# mk312lite_V4.net
KiCad netlist of a schematic drawn in EAGLE
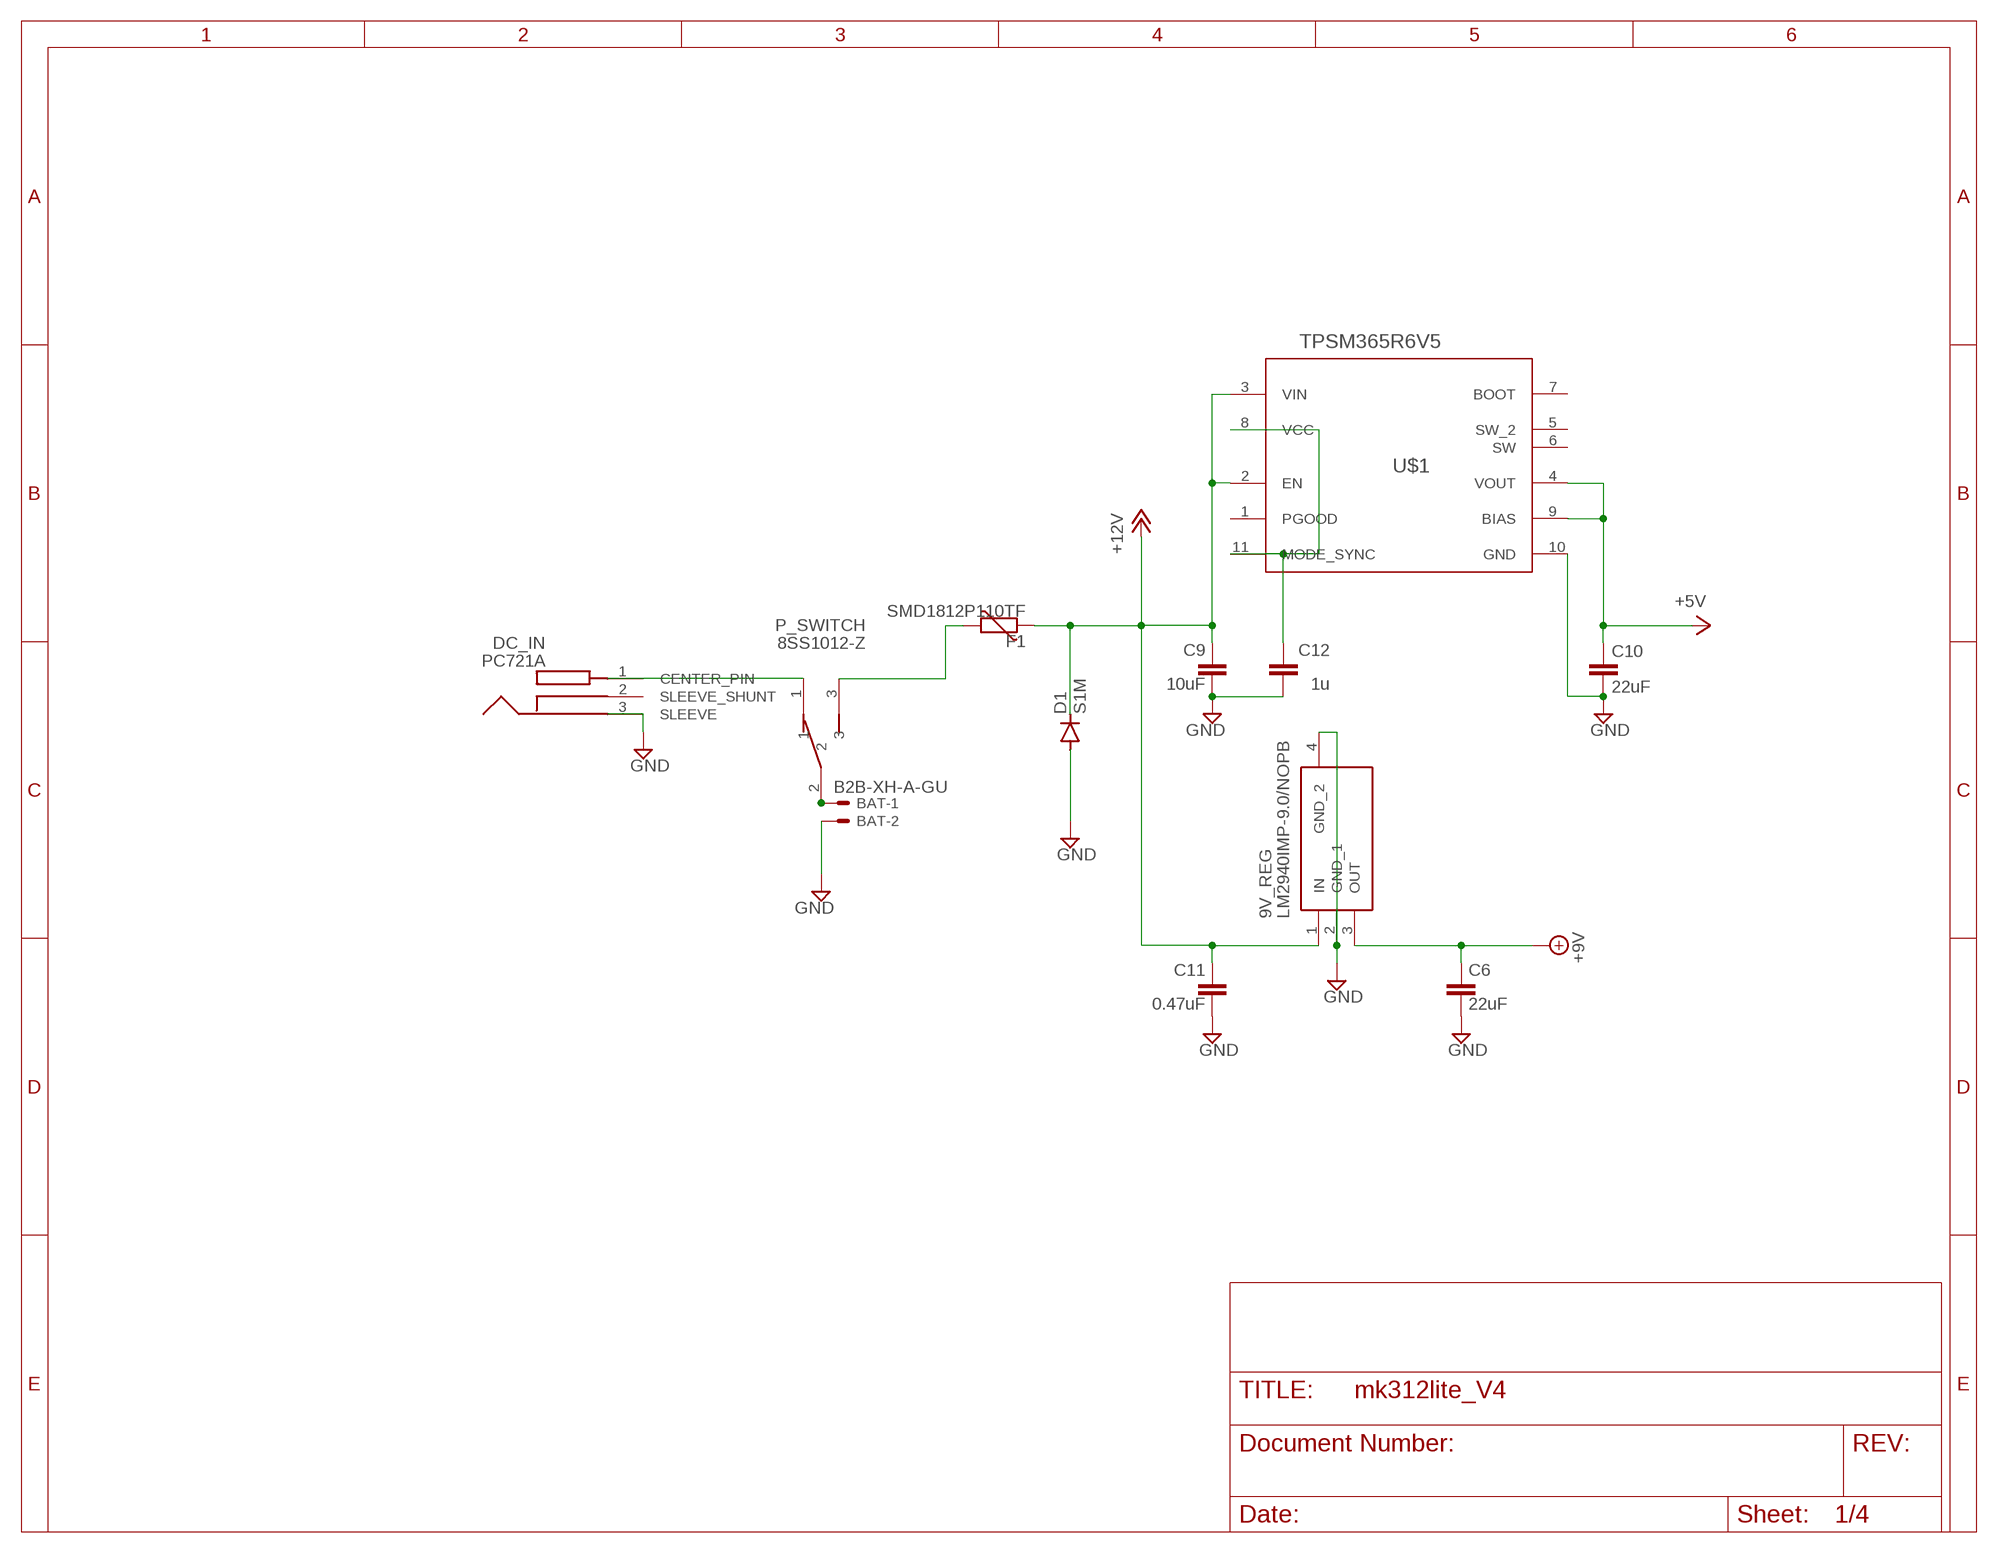
[diagram p0: schematic, sheet 1]
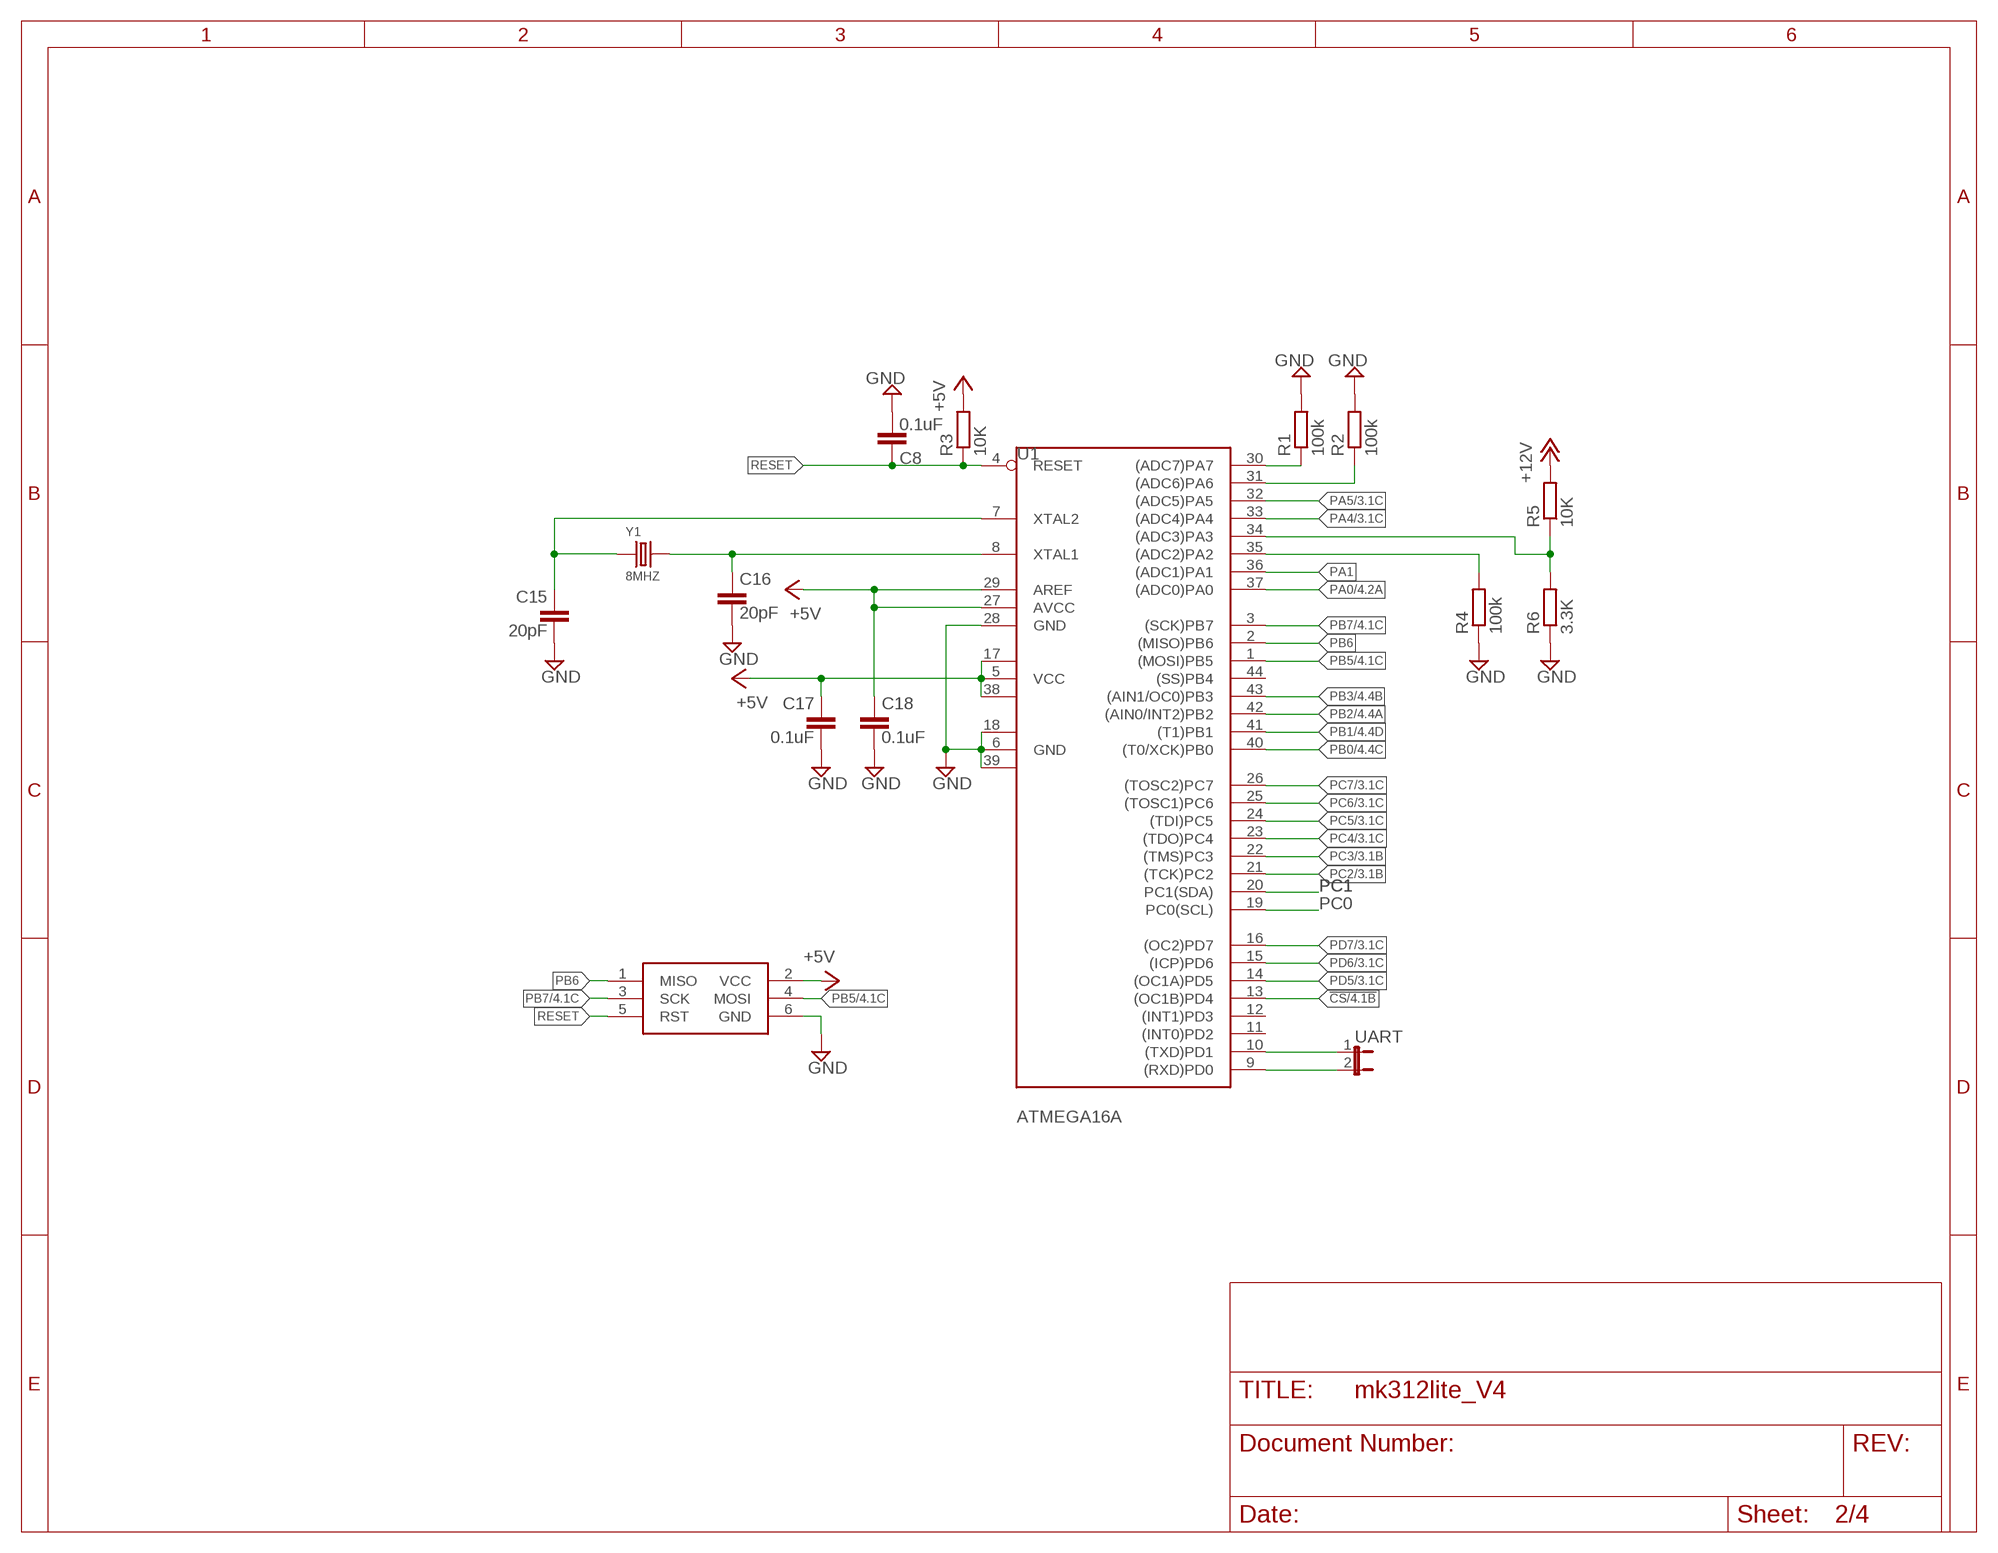
[diagram p1: schematic, sheet 2]
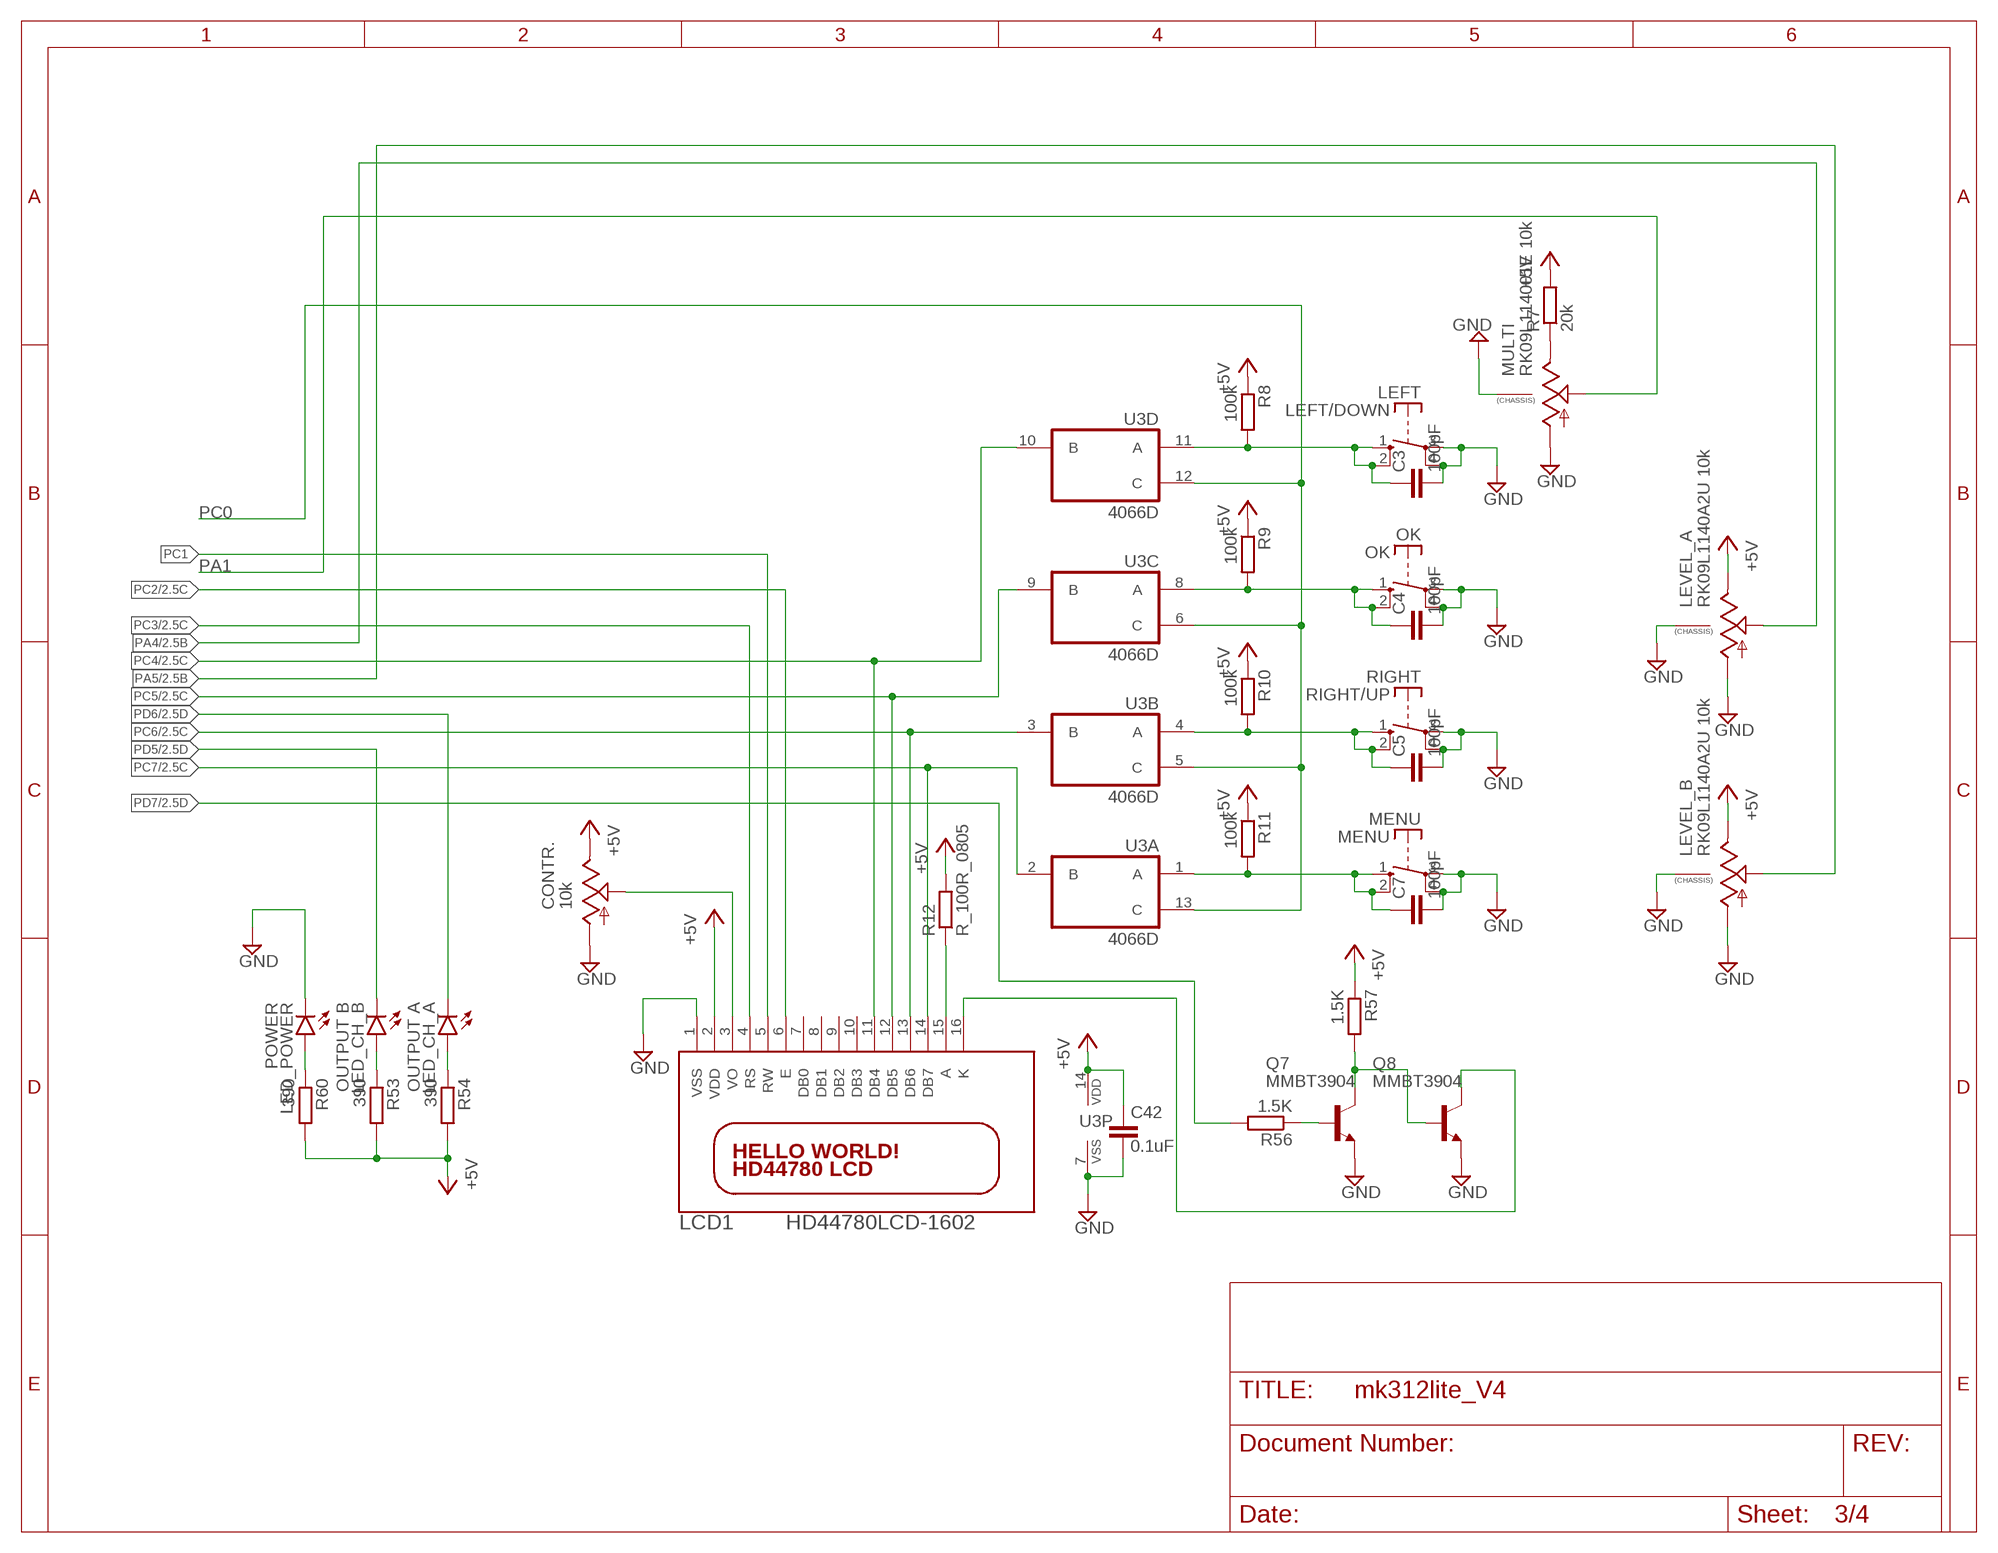
[diagram p2: schematic, sheet 3]
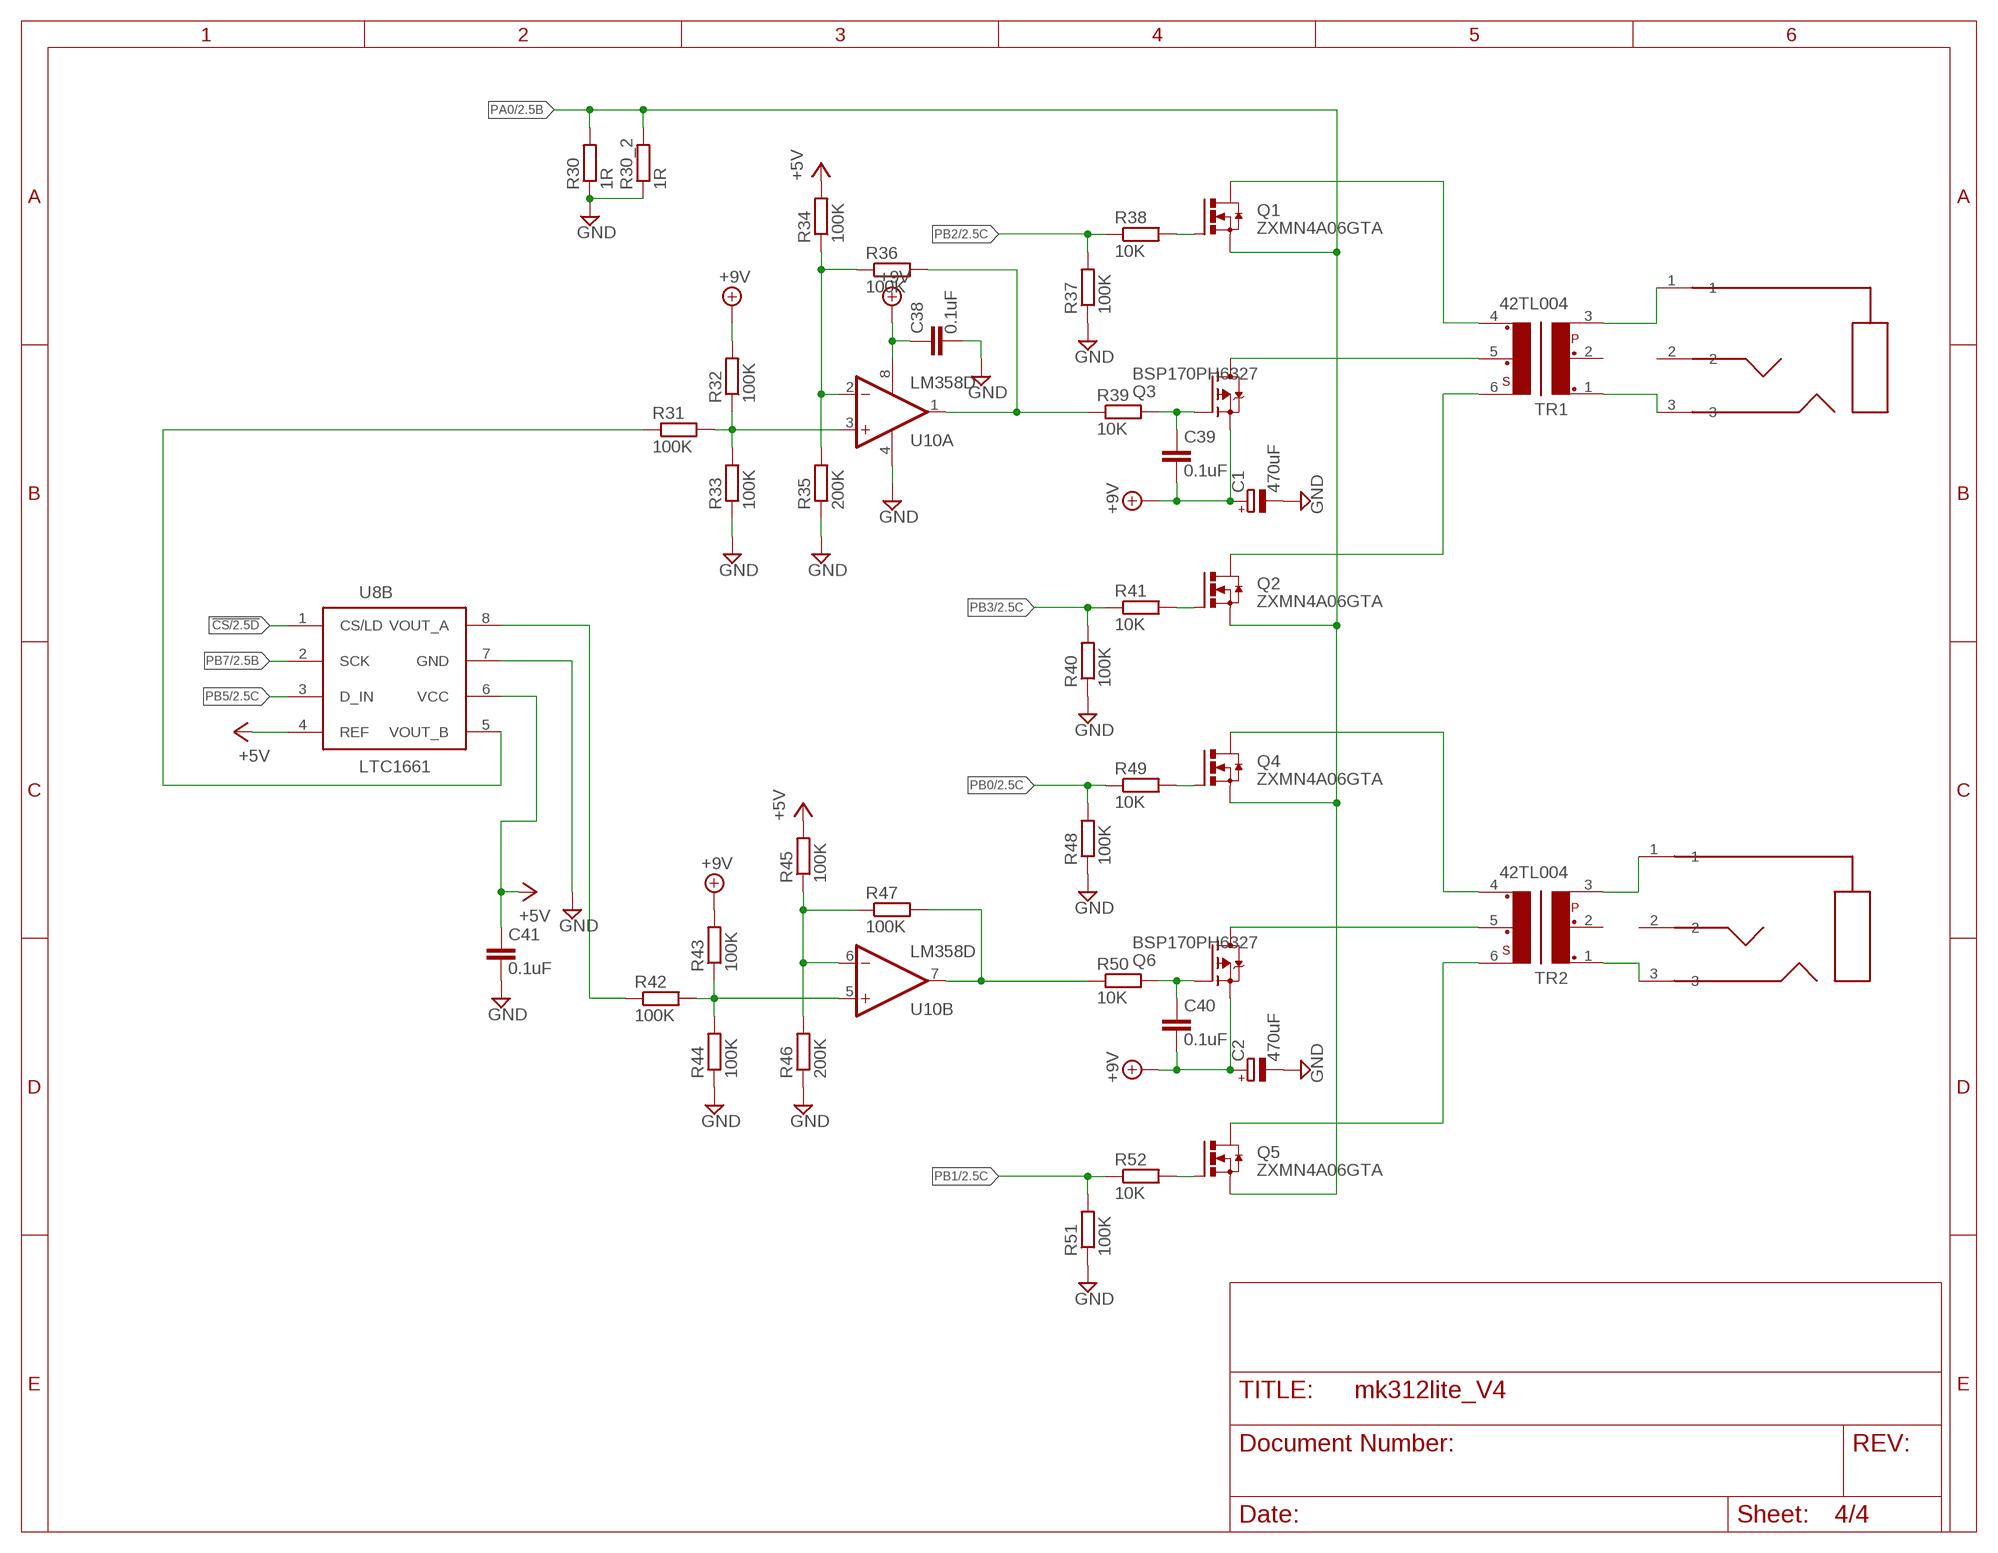
[diagram p3: schematic, sheet 4]

(export (version "E")
  (design (tool "Eeschema 10.0.6"))
  (components
    (comp (ref "9V_REG")
      (value "LM2940IMP-9.0/NOPB")
      (footprint "eagle-import:SOT230P700X180-4N")
      (fields (field (name "MOUSER_PART_NUMBER") "926-LM2940IMP90NOPB"))
      (libsource (lib "eagle-import") (part "LM2940IMP-9.0_NOPB"))
    )
    (comp (ref "BAT")
      (value "B2B-XH-A-GU")
      (footprint "eagle-import:JST-XH-02-PACKAGE-LONG-PAD")
      (libsource (lib "eagle-import") (part "JST-XH-02-PIN-LONG-PAD"))
    )
    (comp (ref "C6")
      (value "22uF")
      (footprint "eagle-import:C1206")
      (libsource (lib "eagle-import") (part "C-EUC1206"))
    )
    (comp (ref "C9")
      (value "10uF")
      (footprint "eagle-import:C0805")
      (libsource (lib "eagle-import") (part "C-EUC0805"))
    )
    (comp (ref "C10")
      (value "22uF")
      (footprint "eagle-import:C1206")
      (libsource (lib "eagle-import") (part "C-EUC1206"))
    )
    (comp (ref "C11")
      (value "0.47uF")
      (footprint "eagle-import:C0805")
      (libsource (lib "eagle-import") (part "C-EUC0805"))
    )
    (comp (ref "C12")
      (value "1u")
      (footprint "eagle-import:C0805")
      (libsource (lib "eagle-import") (part "C-EUC0805"))
    )
    (comp (ref "D1")
      (value "S1M")
      (footprint "eagle-import:SMA")
      (libsource (lib "eagle-import") (part "S1M"))
    )
    (comp (ref "DC_IN")
      (value "PC721A")
      (footprint "eagle-import:PC721A")
      (fields (field (name "MOUSER_PART_NUMBER") "502-PC721A"))
      (libsource (lib "eagle-import") (part "PC721A"))
    )
    (comp (ref "F1")
      (value "SMD1812P110TF")
      (footprint "eagle-import:CT_CN1812")
      (libsource (lib "eagle-import") (part "VARISTORCN1812"))
    )
    (comp (ref "P_SWITCH")
      (value "8SS1012-Z")
      (footprint "eagle-import:8SS1012Z")
      (libsource (lib "eagle-import") (part "8SS1012-Z"))
    )
    (comp (ref "U$1")
      (value "TPSM365R6V5")
      (footprint "eagle-import:RDN0011A-MFG")
      (fields
        (field (name "MANUFACTURER_PART_NUMBER") "PTPSM365R6FRDN")
        (field (name "COPYRIGHT") "Copyright (C) 2025 Ultra Librarian. All rights reserved.")
      )
      (libsource (lib "eagle-import") (part "PTPSM365R6FRDN"))
    )
    (comp (ref "C1")
      (value "470uF")
      (footprint "eagle-import:150CLZ-1010")
      (libsource (lib "eagle-import") (part "CPOL-EU150CLZ-1010"))
    )
    (comp (ref "C2")
      (value "470uF")
      (footprint "eagle-import:150CLZ-1010")
      (libsource (lib "eagle-import") (part "CPOL-EU150CLZ-1010"))
    )
    (comp (ref "C38")
      (value "0.1uF")
      (footprint "eagle-import:C0805")
      (libsource (lib "eagle-import") (part "C-EUC0805"))
    )
    (comp (ref "C39")
      (value "0.1uF")
      (footprint "eagle-import:C0805")
      (libsource (lib "eagle-import") (part "C-EUC0805"))
    )
    (comp (ref "C40")
      (value "0.1uF")
      (footprint "eagle-import:C0805")
      (libsource (lib "eagle-import") (part "C-EUC0805"))
    )
    (comp (ref "C41")
      (value "0.1uF")
      (footprint "eagle-import:C0805")
      (libsource (lib "eagle-import") (part "C-EUC0805"))
    )
    (comp (ref "CHAN_A")
      (value "PJ-301C")
      (footprint "eagle-import:PJ-301C")
      (libsource (lib "eagle-import") (part "PC-301C"))
    )
    (comp (ref "CHAN_B")
      (value "PJ-301C")
      (footprint "eagle-import:PJ-301C")
      (libsource (lib "eagle-import") (part "PC-301C"))
    )
    (comp (ref "Q1")
      (value "ZXMN4A06GTA")
      (footprint "eagle-import:SOT223")
      (libsource (lib "eagle-import") (part "N-HEXFET-2D_?-SOT232IRLL2705"))
    )
    (comp (ref "Q2")
      (value "ZXMN4A06GTA")
      (footprint "eagle-import:SOT223")
      (libsource (lib "eagle-import") (part "N-HEXFET-2D_?-SOT232IRLL2705"))
    )
    (comp (ref "Q3")
      (value "BSP170PH6327")
      (footprint "eagle-import:SOT230P700X180-4N")
      (libsource (lib "eagle-import") (part "IRFL9014TRPBF"))
    )
    (comp (ref "Q4")
      (value "ZXMN4A06GTA")
      (footprint "eagle-import:SOT223")
      (libsource (lib "eagle-import") (part "N-HEXFET-2D_?-SOT232IRLL2705"))
    )
    (comp (ref "Q5")
      (value "ZXMN4A06GTA")
      (footprint "eagle-import:SOT223")
      (libsource (lib "eagle-import") (part "N-HEXFET-2D_?-SOT232IRLL2705"))
    )
    (comp (ref "Q6")
      (value "BSP170PH6327")
      (footprint "eagle-import:SOT230P700X180-4N")
      (libsource (lib "eagle-import") (part "IRFL9014TRPBF"))
    )
    (comp (ref "R30")
      (value "1R")
      (footprint "eagle-import:R1206")
      (libsource (lib "eagle-import") (part "R-EU_R1206"))
    )
    (comp (ref "R30_2")
      (value "1R")
      (footprint "eagle-import:R1206")
      (libsource (lib "eagle-import") (part "R-EU_R1206"))
    )
    (comp (ref "R31")
      (value "100K")
      (footprint "eagle-import:R0805")
      (libsource (lib "eagle-import") (part "R-EU_R0805"))
    )
    (comp (ref "R32")
      (value "100K")
      (footprint "eagle-import:R0805")
      (libsource (lib "eagle-import") (part "R-EU_R0805"))
    )
    (comp (ref "R33")
      (value "100K")
      (footprint "eagle-import:R0805")
      (libsource (lib "eagle-import") (part "R-EU_R0805"))
    )
    (comp (ref "R34")
      (value "100K")
      (footprint "eagle-import:R0805")
      (libsource (lib "eagle-import") (part "R-EU_R0805"))
    )
    (comp (ref "R35")
      (value "200K")
      (footprint "eagle-import:R0805")
      (libsource (lib "eagle-import") (part "R-EU_R0805"))
    )
    (comp (ref "R36")
      (value "100K")
      (footprint "eagle-import:R0805")
      (libsource (lib "eagle-import") (part "R-EU_R0805"))
    )
    (comp (ref "R37")
      (value "100K")
      (footprint "eagle-import:R0805")
      (libsource (lib "eagle-import") (part "R-EU_R0805"))
    )
    (comp (ref "R38")
      (value "10K")
      (footprint "eagle-import:R0805")
      (libsource (lib "eagle-import") (part "R-EU_R0805"))
    )
    (comp (ref "R39")
      (value "10K")
      (footprint "eagle-import:R0805")
      (libsource (lib "eagle-import") (part "R-EU_R0805"))
    )
    (comp (ref "R40")
      (value "100K")
      (footprint "eagle-import:R0805")
      (libsource (lib "eagle-import") (part "R-EU_R0805"))
    )
    (comp (ref "R41")
      (value "10K")
      (footprint "eagle-import:R0805")
      (libsource (lib "eagle-import") (part "R-EU_R0805"))
    )
    (comp (ref "R42")
      (value "100K")
      (footprint "eagle-import:R0805")
      (libsource (lib "eagle-import") (part "R-EU_R0805"))
    )
    (comp (ref "R43")
      (value "100K")
      (footprint "eagle-import:R0805")
      (libsource (lib "eagle-import") (part "R-EU_R0805"))
    )
    (comp (ref "R44")
      (value "100K")
      (footprint "eagle-import:R0805")
      (libsource (lib "eagle-import") (part "R-EU_R0805"))
    )
    (comp (ref "R45")
      (value "100K")
      (footprint "eagle-import:R0805")
      (libsource (lib "eagle-import") (part "R-EU_R0805"))
    )
    (comp (ref "R46")
      (value "200K")
      (footprint "eagle-import:R0805")
      (libsource (lib "eagle-import") (part "R-EU_R0805"))
    )
    (comp (ref "R47")
      (value "100K")
      (footprint "eagle-import:R0805")
      (libsource (lib "eagle-import") (part "R-EU_R0805"))
    )
    (comp (ref "R48")
      (value "100K")
      (footprint "eagle-import:R0805")
      (libsource (lib "eagle-import") (part "R-EU_R0805"))
    )
    (comp (ref "R49")
      (value "10K")
      (footprint "eagle-import:R0805")
      (libsource (lib "eagle-import") (part "R-EU_R0805"))
    )
    (comp (ref "R50")
      (value "10K")
      (footprint "eagle-import:R0805")
      (libsource (lib "eagle-import") (part "R-EU_R0805"))
    )
    (comp (ref "R51")
      (value "100K")
      (footprint "eagle-import:R0805")
      (libsource (lib "eagle-import") (part "R-EU_R0805"))
    )
    (comp (ref "R52")
      (value "10K")
      (footprint "eagle-import:R0805")
      (libsource (lib "eagle-import") (part "R-EU_R0805"))
    )
    (comp (ref "TR1")
      (value "42TL004")
      (footprint "eagle-import:42TL")
      (libsource (lib "eagle-import") (part "42T?L023"))
    )
    (comp (ref "TR2")
      (value "42TL004")
      (footprint "eagle-import:42TL")
      (libsource (lib "eagle-import") (part "42T?L023"))
    )
    (comp (ref "U8B")
      (value "LTC1661")
      (footprint "eagle-import:MSOP8")
      (libsource (lib "eagle-import") (part "LTC1661IMS8"))
    )
    (comp (ref "U10")
      (value "LM358D")
      (footprint "eagle-import:SO08")
      (libsource (lib "eagle-import") (part "LM358D"))
    )
    (comp (ref "C8")
      (value "0.1uF")
      (footprint "eagle-import:C0805")
      (libsource (lib "eagle-import") (part "C-EUC0805"))
    )
    (comp (ref "C15")
      (value "20pF")
      (footprint "eagle-import:C0603")
      (libsource (lib "eagle-import") (part "C-EUC0603"))
    )
    (comp (ref "C16")
      (value "20pF")
      (footprint "eagle-import:C0603")
      (libsource (lib "eagle-import") (part "C-EUC0603"))
    )
    (comp (ref "C17")
      (value "0.1uF")
      (footprint "eagle-import:C0805")
      (libsource (lib "eagle-import") (part "C-EUC0805"))
    )
    (comp (ref "C18")
      (value "0.1uF")
      (footprint "eagle-import:C0805")
      (libsource (lib "eagle-import") (part "C-EUC0805"))
    )
    (comp (ref "ISP1")
      (value "AVRISP-6")
      (footprint "eagle-import:AVRISP")
      (libsource (lib "eagle-import") (part "AVRISP-6"))
    )
    (comp (ref "R1")
      (value "100k")
      (footprint "eagle-import:R0805")
      (libsource (lib "eagle-import") (part "R-EU_R0805"))
    )
    (comp (ref "R2")
      (value "100k")
      (footprint "eagle-import:R0805")
      (libsource (lib "eagle-import") (part "R-EU_R0805"))
    )
    (comp (ref "R3")
      (value "10K")
      (footprint "eagle-import:R0805")
      (libsource (lib "eagle-import") (part "R-EU_R0805"))
    )
    (comp (ref "R4")
      (value "100k")
      (footprint "eagle-import:R0805")
      (libsource (lib "eagle-import") (part "R-EU_R0805"))
    )
    (comp (ref "R5")
      (value "10K")
      (footprint "eagle-import:R0805")
      (libsource (lib "eagle-import") (part "R-EU_R0805"))
    )
    (comp (ref "R6")
      (value "3.3K")
      (footprint "eagle-import:R0805")
      (libsource (lib "eagle-import") (part "R-EU_R0805"))
    )
    (comp (ref "U1")
      (value "ATMEGA16A")
      (footprint "eagle-import:TQFP44")
      (fields (field (name "MPN") "ATMEGA16-16AU"))
      (libsource (lib "eagle-import") (part "MEGA16-A"))
    )
    (comp (ref "UART")
      (value "JP1E")
      (footprint "eagle-import:JP1")
      (libsource (lib "eagle-import") (part "JP1E"))
    )
    (comp (ref "Y1")
      (value "8MHZ")
      (footprint "eagle-import:X2-SMD-5.0X3.2X1.3MM")
      (fields (field (name "MPN") "5032/2P"))
      (libsource (lib "eagle-import") (part "SMD-CRYSTAL-8MHZ-20PF-20PPM(2P-5.0X3.2MM)"))
    )
    (comp (ref "C3")
      (value "100pF")
      (footprint "eagle-import:C0805")
      (libsource (lib "eagle-import") (part "C-EUC0805"))
    )
    (comp (ref "C4")
      (value "100pF")
      (footprint "eagle-import:C0805")
      (libsource (lib "eagle-import") (part "C-EUC0805"))
    )
    (comp (ref "C5")
      (value "100pF")
      (footprint "eagle-import:C0805")
      (libsource (lib "eagle-import") (part "C-EUC0805"))
    )
    (comp (ref "C7")
      (value "100pF")
      (footprint "eagle-import:C0805")
      (libsource (lib "eagle-import") (part "C-EUC0805"))
    )
    (comp (ref "C42")
      (value "0.1uF")
      (footprint "eagle-import:C0805")
      (libsource (lib "eagle-import") (part "C-EUC0805"))
    )
    (comp (ref "CONTR.")
      (value "10k")
      (footprint "eagle-import:B25P")
      (libsource (lib "eagle-import") (part "TRIM_US-B25P"))
    )
    (comp (ref "LCD1")
      (value "HD44780LCD-1602")
      (footprint "eagle-import:LCD1602")
      (libsource (lib "eagle-import") (part "HD44780LCD-1602"))
    )
    (comp (ref "LED_CH_A")
      (value "OUTPUT A")
      (footprint "eagle-import:LED3MM")
      (libsource (lib "eagle-import") (part "LED3MM"))
    )
    (comp (ref "LED_CH_B")
      (value "OUTPUT B")
      (footprint "eagle-import:LED3MM")
      (libsource (lib "eagle-import") (part "LED3MM"))
    )
    (comp (ref "LED_POWER")
      (value "POWER")
      (footprint "eagle-import:LED3MM")
      (libsource (lib "eagle-import") (part "LED3MM"))
    )
    (comp (ref "LEFT")
      (value "LEFT/DOWN")
      (footprint "eagle-import:DTE6K")
      (libsource (lib "eagle-import") (part "DTE6K"))
    )
    (comp (ref "LEVEL_A")
      (value "RK09L1140A2U 10k")
      (footprint "eagle-import:9MM_SNAP-IN_POT")
      (libsource (lib "eagle-import") (part "9MM_SNAP-IN_POT_CHASSIS"))
    )
    (comp (ref "LEVEL_B")
      (value "RK09L1140A2U 10k")
      (footprint "eagle-import:9MM_SNAP-IN_POT")
      (libsource (lib "eagle-import") (part "9MM_SNAP-IN_POT_CHASSIS"))
    )
    (comp (ref "MENU")
      (value "MENU")
      (footprint "eagle-import:DTE6K")
      (libsource (lib "eagle-import") (part "DTE6K"))
    )
    (comp (ref "MULTI")
      (value "RK09L114001E 10k")
      (footprint "eagle-import:9MM_SNAP-IN_POT")
      (libsource (lib "eagle-import") (part "9MM_SNAP-IN_POT_CHASSIS"))
    )
    (comp (ref "OK")
      (value "OK")
      (footprint "eagle-import:DTE6K")
      (libsource (lib "eagle-import") (part "DTE6K"))
    )
    (comp (ref "Q7")
      (value "MMBT3904")
      (footprint "eagle-import:SOT23-BEC")
      (libsource (lib "eagle-import") (part "-NPN-SOT23-BECMMBT3904LT1"))
    )
    (comp (ref "Q8")
      (value "MMBT3904")
      (footprint "eagle-import:SOT23-BEC")
      (libsource (lib "eagle-import") (part "-NPN-SOT23-BECMMBT3904LT1"))
    )
    (comp (ref "R7")
      (value "20k")
      (footprint "eagle-import:R0805")
      (libsource (lib "eagle-import") (part "R-EU_R0805"))
    )
    (comp (ref "R8")
      (value "100k")
      (footprint "eagle-import:R0805")
      (libsource (lib "eagle-import") (part "R-EU_R0805"))
    )
    (comp (ref "R9")
      (value "100k")
      (footprint "eagle-import:R0805")
      (libsource (lib "eagle-import") (part "R-EU_R0805"))
    )
    (comp (ref "R10")
      (value "100k")
      (footprint "eagle-import:R0805")
      (libsource (lib "eagle-import") (part "R-EU_R0805"))
    )
    (comp (ref "R11")
      (value "100k")
      (footprint "eagle-import:R0805")
      (libsource (lib "eagle-import") (part "R-EU_R0805"))
    )
    (comp (ref "R12")
      (value "R_100R_0805")
      (footprint "eagle-import:R0805")
      (fields (field (name "LCSC_PART") "C17408"))
      (libsource (lib "eagle-import") (part "R__0805100R"))
    )
    (comp (ref "R53")
      (value "390")
      (footprint "eagle-import:R0805")
      (libsource (lib "eagle-import") (part "R-EU_R0805"))
    )
    (comp (ref "R54")
      (value "390")
      (footprint "eagle-import:R0805")
      (libsource (lib "eagle-import") (part "R-EU_R0805"))
    )
    (comp (ref "R56")
      (value "1.5K")
      (footprint "eagle-import:R0805")
      (libsource (lib "eagle-import") (part "R-EU_R0805"))
    )
    (comp (ref "R57")
      (value "1.5K")
      (footprint "eagle-import:R0805")
      (libsource (lib "eagle-import") (part "R-EU_R0805"))
    )
    (comp (ref "R60")
      (value "390")
      (footprint "eagle-import:R0805")
      (libsource (lib "eagle-import") (part "R-EU_R0805"))
    )
    (comp (ref "RIGHT")
      (value "RIGHT/UP")
      (footprint "eagle-import:DTE6K")
      (libsource (lib "eagle-import") (part "DTE6K"))
    )
    (comp (ref "U3")
      (value "4066D")
      (footprint "eagle-import:SO14")
      (libsource (lib "eagle-import") (part "4066D"))
    )
  )
  (nets
    (net (code "1") (name "+5V") (class "Default")
      (node (ref "C10") (pin "1") (pinfunction "1_1") (pintype "passive"))
      (node (ref "C17") (pin "1") (pinfunction "1_1") (pintype "passive"))
      (node (ref "C18") (pin "1") (pinfunction "1_1") (pintype "passive"))
      (node (ref "C41") (pin "1") (pinfunction "1_1") (pintype "passive"))
      (node (ref "C42") (pin "1") (pinfunction "1_1") (pintype "passive"))
      (node (ref "CONTR.") (pin "E") (pinfunction "E_E") (pintype "passive"))
      (node (ref "ISP1") (pin "2") (pinfunction "VCC_2") (pintype "power_in"))
      (node (ref "LCD1") (pin "2") (pinfunction "VDD_2") (pintype "power_in"))
      (node (ref "LEVEL_A") (pin "3") (pinfunction "E_3") (pintype "passive"))
      (node (ref "LEVEL_B") (pin "3") (pinfunction "E_3") (pintype "passive"))
      (node (ref "R10") (pin "1") (pinfunction "1_1") (pintype "passive"))
      (node (ref "R11") (pin "1") (pinfunction "1_1") (pintype "passive"))
      (node (ref "R12") (pin "2") (pinfunction "2_2") (pintype "passive"))
      (node (ref "R3") (pin "2") (pinfunction "2_2") (pintype "passive"))
      (node (ref "R34") (pin "2") (pinfunction "2_2") (pintype "passive"))
      (node (ref "R45") (pin "2") (pinfunction "2_2") (pintype "passive"))
      (node (ref "R53") (pin "2") (pinfunction "2_2") (pintype "passive"))
      (node (ref "R54") (pin "2") (pinfunction "2_2") (pintype "passive"))
      (node (ref "R57") (pin "1") (pinfunction "1_1") (pintype "passive"))
      (node (ref "R60") (pin "2") (pinfunction "2_2") (pintype "passive"))
      (node (ref "R7") (pin "2") (pinfunction "2_2") (pintype "passive"))
      (node (ref "R8") (pin "1") (pinfunction "1_1") (pintype "passive"))
      (node (ref "R9") (pin "1") (pinfunction "1_1") (pintype "passive"))
      (node (ref "U$1") (pin "4") (pinfunction "VOUT_4") (pintype "passive"))
      (node (ref "U$1") (pin "9") (pinfunction "BIAS_9") (pintype "passive"))
      (node (ref "U1") (pin "17") (pinfunction "VCC1_17") (pintype "power_in"))
      (node (ref "U1") (pin "27") (pinfunction "AVCC_27") (pintype "power_in"))
      (node (ref "U1") (pin "29") (pinfunction "AREF_29") (pintype "passive"))
      (node (ref "U1") (pin "38") (pinfunction "VCC2_38") (pintype "power_in"))
      (node (ref "U1") (pin "5") (pinfunction "VCC_5") (pintype "power_in"))
      (node (ref "U3") (pin "14") (pinfunction "VDD_14") (pintype "power_in"))
      (node (ref "U8B") (pin "4") (pinfunction "REF_4") (pintype "input"))
      (node (ref "U8B") (pin "6") (pinfunction "VCC_6") (pintype "power_in"))
    )
    (net (code "2") (name "+9V") (class "Default")
      (node (ref "9V_REG") (pin "3") (pinfunction "OUT_3") (pintype "bidirectional"))
      (node (ref "C1") (pin "+") (pinfunction "+_+") (pintype "passive"))
      (node (ref "C2") (pin "+") (pinfunction "+_+") (pintype "passive"))
      (node (ref "C38") (pin "1") (pinfunction "1_1") (pintype "passive"))
      (node (ref "C39") (pin "2") (pinfunction "2_2") (pintype "passive"))
      (node (ref "C40") (pin "2") (pinfunction "2_2") (pintype "passive"))
      (node (ref "C6") (pin "1") (pinfunction "1_1") (pintype "passive"))
      (node (ref "Q3") (pin "3") (pinfunction "S_3") (pintype "passive"))
      (node (ref "Q6") (pin "3") (pinfunction "S_3") (pintype "passive"))
      (node (ref "R32") (pin "2") (pinfunction "2_2") (pintype "passive"))
      (node (ref "R43") (pin "2") (pinfunction "2_2") (pintype "passive"))
      (node (ref "U10") (pin "8") (pinfunction "V+_8") (pintype "power_in"))
    )
    (net (code "3") (name "+12V") (class "Default")
      (node (ref "9V_REG") (pin "1") (pinfunction "IN_1") (pintype "bidirectional"))
      (node (ref "C11") (pin "1") (pinfunction "1_1") (pintype "passive"))
      (node (ref "C9") (pin "1") (pinfunction "1_1") (pintype "passive"))
      (node (ref "D1") (pin "C") (pinfunction "C_C") (pintype "passive"))
      (node (ref "F1") (pin "2") (pinfunction "2_2") (pintype "passive"))
      (node (ref "R5") (pin "2") (pinfunction "2_2") (pintype "passive"))
      (node (ref "U$1") (pin "2") (pinfunction "EN_2") (pintype "input"))
      (node (ref "U$1") (pin "3") (pinfunction "VIN_3") (pintype "power_in"))
    )
    (net (code "4") (name "GND") (class "Default")
      (node (ref "9V_REG") (pin "2") (pinfunction "GND_1_2") (pintype "bidirectional"))
      (node (ref "9V_REG") (pin "4") (pinfunction "GND_2_4") (pintype "bidirectional"))
      (node (ref "BAT") (pin "2") (pinfunction "S_2") (pintype "passive"))
      (node (ref "C1") (pin "-") (pinfunction "-_-") (pintype "passive"))
      (node (ref "C10") (pin "2") (pinfunction "2_2") (pintype "passive"))
      (node (ref "C11") (pin "2") (pinfunction "2_2") (pintype "passive"))
      (node (ref "C12") (pin "2") (pinfunction "2_2") (pintype "passive"))
      (node (ref "C15") (pin "2") (pinfunction "2_2") (pintype "passive"))
      (node (ref "C16") (pin "2") (pinfunction "2_2") (pintype "passive"))
      (node (ref "C17") (pin "2") (pinfunction "2_2") (pintype "passive"))
      (node (ref "C18") (pin "2") (pinfunction "2_2") (pintype "passive"))
      (node (ref "C2") (pin "-") (pinfunction "-_-") (pintype "passive"))
      (node (ref "C3") (pin "2") (pinfunction "2_2") (pintype "passive"))
      (node (ref "C38") (pin "2") (pinfunction "2_2") (pintype "passive"))
      (node (ref "C4") (pin "2") (pinfunction "2_2") (pintype "passive"))
      (node (ref "C41") (pin "2") (pinfunction "2_2") (pintype "passive"))
      (node (ref "C42") (pin "2") (pinfunction "2_2") (pintype "passive"))
      (node (ref "C5") (pin "2") (pinfunction "2_2") (pintype "passive"))
      (node (ref "C6") (pin "2") (pinfunction "2_2") (pintype "passive"))
      (node (ref "C7") (pin "2") (pinfunction "2_2") (pintype "passive"))
      (node (ref "C8") (pin "2") (pinfunction "2_2") (pintype "passive"))
      (node (ref "C9") (pin "2") (pinfunction "2_2") (pintype "passive"))
      (node (ref "CONTR.") (pin "A") (pinfunction "A_A") (pintype "passive"))
      (node (ref "D1") (pin "A") (pinfunction "A_A") (pintype "passive"))
      (node (ref "DC_IN") (pin "3") (pinfunction "SLEEVE_3") (pintype "bidirectional"))
      (node (ref "ISP1") (pin "6") (pinfunction "GND_6") (pintype "power_in"))
      (node (ref "LCD1") (pin "1") (pinfunction "VSS_1") (pintype "power_in"))
      (node (ref "LED_POWER") (pin "K") (pinfunction "C_K") (pintype "passive"))
      (node (ref "LEFT") (pin "3") (pinfunction "P_3") (pintype "passive"))
      (node (ref "LEFT") (pin "4") (pinfunction "P_4") (pintype "passive"))
      (node (ref "LEVEL_A") (pin "1") (pinfunction "A_1") (pintype "passive"))
      (node (ref "LEVEL_A") (pin "CHASSIS2") (pinfunction "P$1_CHASSIS2") (pintype "passive"))
      (node (ref "LEVEL_B") (pin "1") (pinfunction "A_1") (pintype "passive"))
      (node (ref "LEVEL_B") (pin "CHASSIS2") (pinfunction "P$1_CHASSIS2") (pintype "passive"))
      (node (ref "MENU") (pin "3") (pinfunction "P_3") (pintype "passive"))
      (node (ref "MENU") (pin "4") (pinfunction "P_4") (pintype "passive"))
      (node (ref "MULTI") (pin "1") (pinfunction "A_1") (pintype "passive"))
      (node (ref "MULTI") (pin "CHASSIS2") (pinfunction "P$1_CHASSIS2") (pintype "passive"))
      (node (ref "OK") (pin "3") (pinfunction "P_3") (pintype "passive"))
      (node (ref "OK") (pin "4") (pinfunction "P_4") (pintype "passive"))
      (node (ref "Q7") (pin "E") (pinfunction "E_E") (pintype "passive"))
      (node (ref "Q8") (pin "E") (pinfunction "E_E") (pintype "passive"))
      (node (ref "R1") (pin "2") (pinfunction "2_2") (pintype "passive"))
      (node (ref "R2") (pin "2") (pinfunction "2_2") (pintype "passive"))
      (node (ref "R30") (pin "1") (pinfunction "1_1") (pintype "passive"))
      (node (ref "R30_2") (pin "1") (pinfunction "1_1") (pintype "passive"))
      (node (ref "R33") (pin "1") (pinfunction "1_1") (pintype "passive"))
      (node (ref "R35") (pin "1") (pinfunction "1_1") (pintype "passive"))
      (node (ref "R37") (pin "1") (pinfunction "1_1") (pintype "passive"))
      (node (ref "R4") (pin "1") (pinfunction "1_1") (pintype "passive"))
      (node (ref "R40") (pin "1") (pinfunction "1_1") (pintype "passive"))
      (node (ref "R44") (pin "1") (pinfunction "1_1") (pintype "passive"))
      (node (ref "R46") (pin "1") (pinfunction "1_1") (pintype "passive"))
      (node (ref "R48") (pin "1") (pinfunction "1_1") (pintype "passive"))
      (node (ref "R51") (pin "1") (pinfunction "1_1") (pintype "passive"))
      (node (ref "R6") (pin "1") (pinfunction "1_1") (pintype "passive"))
      (node (ref "RIGHT") (pin "3") (pinfunction "P_3") (pintype "passive"))
      (node (ref "RIGHT") (pin "4") (pinfunction "P_4") (pintype "passive"))
      (node (ref "U$1") (pin "10") (pinfunction "GND_10") (pintype "power_in"))
      (node (ref "U1") (pin "18") (pinfunction "GND1_18") (pintype "power_in"))
      (node (ref "U1") (pin "28") (pinfunction "GND_28") (pintype "power_in"))
      (node (ref "U1") (pin "39") (pinfunction "GND2_39") (pintype "power_in"))
      (node (ref "U1") (pin "6") (pinfunction "GND_6") (pintype "power_in"))
      (node (ref "U10") (pin "4") (pinfunction "V-_4") (pintype "power_in"))
      (node (ref "U3") (pin "7") (pinfunction "VSS_7") (pintype "power_in"))
      (node (ref "U8B") (pin "7") (pinfunction "GND_7") (pintype "power_in"))
    )
    (net (code "5") (name "Net-(BATA-S)") (class "Default")
      (node (ref "BAT") (pin "1") (pinfunction "S_1") (pintype "passive"))
      (node (ref "P_SWITCH") (pin "2") (pinfunction "2_2") (pintype "bidirectional"))
    )
    (net (code "6") (name "Net-(CHAN_A-Pad1)") (class "Default")
      (node (ref "CHAN_A") (pin "1") (pinfunction "1_1") (pintype "bidirectional"))
      (node (ref "TR1") (pin "3") (pinfunction "3_3") (pintype "passive"))
    )
    (net (code "7") (name "Net-(CHAN_A-Pad3)") (class "Default")
      (node (ref "CHAN_A") (pin "3") (pinfunction "3_3") (pintype "bidirectional"))
      (node (ref "TR1") (pin "1") (pinfunction "1_1") (pintype "passive"))
    )
    (net (code "8") (name "Net-(CHAN_B-Pad1)") (class "Default")
      (node (ref "CHAN_B") (pin "1") (pinfunction "1_1") (pintype "bidirectional"))
      (node (ref "TR2") (pin "3") (pinfunction "3_3") (pintype "passive"))
    )
    (net (code "9") (name "Net-(CHAN_B-Pad3)") (class "Default")
      (node (ref "CHAN_B") (pin "3") (pinfunction "3_3") (pintype "bidirectional"))
      (node (ref "TR2") (pin "1") (pinfunction "1_1") (pintype "passive"))
    )
    (net (code "10") (name "Net-(DC_IN-CENTER_PIN)") (class "Default")
      (node (ref "DC_IN") (pin "1") (pinfunction "CENTER_PIN_1") (pintype "bidirectional"))
      (node (ref "P_SWITCH") (pin "1") (pinfunction "1_1") (pintype "bidirectional"))
    )
    (net (code "11") (name "Net-(F1-Pad1)") (class "Default")
      (node (ref "F1") (pin "1") (pinfunction "1_1") (pintype "passive"))
      (node (ref "P_SWITCH") (pin "3") (pinfunction "3_3") (pintype "bidirectional"))
    )
    (net (code "12") (name "Net-(LCD1-A)") (class "Default")
      (node (ref "LCD1") (pin "15") (pinfunction "A_15") (pintype "input"))
      (node (ref "R12") (pin "1") (pinfunction "1_1") (pintype "passive"))
    )
    (net (code "13") (name "Net-(LCD1-K)") (class "Default")
      (node (ref "LCD1") (pin "16") (pinfunction "K_16") (pintype "input"))
      (node (ref "Q8") (pin "C") (pinfunction "C_C") (pintype "passive"))
    )
    (net (code "14") (name "Net-(LCD1-VO)") (class "Default")
      (node (ref "CONTR.") (pin "S") (pinfunction "S_S") (pintype "passive"))
      (node (ref "LCD1") (pin "3") (pinfunction "VO_3") (pintype "input"))
    )
    (net (code "15") (name "Net-(LED_CH_A-PadA)") (class "Default")
      (node (ref "LED_CH_A") (pin "A") (pinfunction "A_A") (pintype "passive"))
      (node (ref "R54") (pin "1") (pinfunction "1_1") (pintype "passive"))
    )
    (net (code "16") (name "Net-(LED_CH_B-PadA)") (class "Default")
      (node (ref "LED_CH_B") (pin "A") (pinfunction "A_A") (pintype "passive"))
      (node (ref "R53") (pin "1") (pinfunction "1_1") (pintype "passive"))
    )
    (net (code "17") (name "Net-(LED_POWER-PadA)") (class "Default")
      (node (ref "LED_POWER") (pin "A") (pinfunction "A_A") (pintype "passive"))
      (node (ref "R60") (pin "1") (pinfunction "1_1") (pintype "passive"))
    )
    (net (code "18") (name "Net-(MULTI-E)") (class "Default")
      (node (ref "MULTI") (pin "3") (pinfunction "E_3") (pintype "passive"))
      (node (ref "R7") (pin "1") (pinfunction "1_1") (pintype "passive"))
    )
    (net (code "19") (name "Net-(Q1-D-Pad2)") (class "Default")
      (node (ref "Q1") (pin "2") (pinfunction "D_2") (pintype "passive"))
      (node (ref "Q1") (pin "4") (pinfunction "D_4") (pintype "passive"))
      (node (ref "TR1") (pin "4") (pinfunction "4_4") (pintype "passive"))
    )
    (net (code "20") (name "Net-(Q1-G)") (class "Default")
      (node (ref "Q1") (pin "1") (pinfunction "G_1") (pintype "passive"))
      (node (ref "R38") (pin "2") (pinfunction "2_2") (pintype "passive"))
    )
    (net (code "21") (name "Net-(Q2-D-Pad2)") (class "Default")
      (node (ref "Q2") (pin "2") (pinfunction "D_2") (pintype "passive"))
      (node (ref "Q2") (pin "4") (pinfunction "D_4") (pintype "passive"))
      (node (ref "TR1") (pin "6") (pinfunction "6_6") (pintype "passive"))
    )
    (net (code "22") (name "Net-(Q2-G)") (class "Default")
      (node (ref "Q2") (pin "1") (pinfunction "G_1") (pintype "passive"))
      (node (ref "R41") (pin "2") (pinfunction "2_2") (pintype "passive"))
    )
    (net (code "23") (name "Net-(Q3-D-Pad2)") (class "Default")
      (node (ref "Q3") (pin "2") (pinfunction "D_2") (pintype "passive"))
      (node (ref "Q3") (pin "4") (pinfunction "D_4") (pintype "passive"))
      (node (ref "TR1") (pin "5") (pinfunction "5_5") (pintype "passive"))
    )
    (net (code "24") (name "Net-(Q3-G)") (class "Default")
      (node (ref "C39") (pin "1") (pinfunction "1_1") (pintype "passive"))
      (node (ref "Q3") (pin "1") (pinfunction "G_1") (pintype "passive"))
      (node (ref "R39") (pin "2") (pinfunction "2_2") (pintype "passive"))
    )
    (net (code "25") (name "Net-(Q4-D-Pad2)") (class "Default")
      (node (ref "Q4") (pin "2") (pinfunction "D_2") (pintype "passive"))
      (node (ref "Q4") (pin "4") (pinfunction "D_4") (pintype "passive"))
      (node (ref "TR2") (pin "4") (pinfunction "4_4") (pintype "passive"))
    )
    (net (code "26") (name "Net-(Q4-G)") (class "Default")
      (node (ref "Q4") (pin "1") (pinfunction "G_1") (pintype "passive"))
      (node (ref "R49") (pin "2") (pinfunction "2_2") (pintype "passive"))
    )
    (net (code "27") (name "Net-(Q5-D-Pad2)") (class "Default")
      (node (ref "Q5") (pin "2") (pinfunction "D_2") (pintype "passive"))
      (node (ref "Q5") (pin "4") (pinfunction "D_4") (pintype "passive"))
      (node (ref "TR2") (pin "6") (pinfunction "6_6") (pintype "passive"))
    )
    (net (code "28") (name "Net-(Q5-G)") (class "Default")
      (node (ref "Q5") (pin "1") (pinfunction "G_1") (pintype "passive"))
      (node (ref "R52") (pin "2") (pinfunction "2_2") (pintype "passive"))
    )
    (net (code "29") (name "Net-(Q6-D-Pad2)") (class "Default")
      (node (ref "Q6") (pin "2") (pinfunction "D_2") (pintype "passive"))
      (node (ref "Q6") (pin "4") (pinfunction "D_4") (pintype "passive"))
      (node (ref "TR2") (pin "5") (pinfunction "5_5") (pintype "passive"))
    )
    (net (code "30") (name "Net-(Q6-G)") (class "Default")
      (node (ref "C40") (pin "1") (pinfunction "1_1") (pintype "passive"))
      (node (ref "Q6") (pin "1") (pinfunction "G_1") (pintype "passive"))
      (node (ref "R50") (pin "2") (pinfunction "2_2") (pintype "passive"))
    )
    (net (code "31") (name "Net-(Q7-PadB)") (class "Default")
      (node (ref "Q7") (pin "B") (pinfunction "B_B") (pintype "passive"))
      (node (ref "R56") (pin "1") (pinfunction "1_1") (pintype "passive"))
    )
    (net (code "32") (name "Net-(Q7-PadC)") (class "Default")
      (node (ref "Q7") (pin "C") (pinfunction "C_C") (pintype "passive"))
      (node (ref "Q8") (pin "B") (pinfunction "B_B") (pintype "passive"))
      (node (ref "R57") (pin "2") (pinfunction "2_2") (pintype "passive"))
    )
    (net (code "33") (name "Net-(U$1-MODE_SYNC)") (class "Default")
      (node (ref "C12") (pin "1") (pinfunction "1_1") (pintype "passive"))
      (node (ref "U$1") (pin "11") (pinfunction "MODE_SYNC_11") (pintype "passive"))
      (node (ref "U$1") (pin "8") (pinfunction "VCC_8") (pintype "passive"))
    )
    (net (code "34") (name "Net-(U1-(ADC2)PA2)") (class "Default")
      (node (ref "R4") (pin "2") (pinfunction "2_2") (pintype "passive"))
      (node (ref "U1") (pin "35") (pinfunction "(ADC2)PA2_35") (pintype "bidirectional"))
    )
    (net (code "35") (name "Net-(U1-(ADC3)PA3)") (class "Default")
      (node (ref "R5") (pin "1") (pinfunction "1_1") (pintype "passive"))
      (node (ref "R6") (pin "2") (pinfunction "2_2") (pintype "passive"))
      (node (ref "U1") (pin "34") (pinfunction "(ADC3)PA3_34") (pintype "bidirectional"))
    )
    (net (code "36") (name "Net-(U1-(ADC6)PA6)") (class "Default")
      (node (ref "R2") (pin "1") (pinfunction "1_1") (pintype "passive"))
      (node (ref "U1") (pin "31") (pinfunction "(ADC6)PA6_31") (pintype "bidirectional"))
    )
    (net (code "37") (name "Net-(U1-(ADC7)PA7)") (class "Default")
      (node (ref "R1") (pin "1") (pinfunction "1_1") (pintype "passive"))
      (node (ref "U1") (pin "30") (pinfunction "(ADC7)PA7_30") (pintype "bidirectional"))
    )
    (net (code "38") (name "Net-(U1-(RXD)PD0)") (class "Default")
      (node (ref "U1") (pin "9") (pinfunction "(RXD)PD0_9") (pintype "bidirectional"))
      (node (ref "UART") (pin "2") (pinfunction "2_2") (pintype "passive"))
    )
    (net (code "39") (name "Net-(U1-(TXD)PD1)") (class "Default")
      (node (ref "U1") (pin "10") (pinfunction "(TXD)PD1_10") (pintype "bidirectional"))
      (node (ref "UART") (pin "1") (pinfunction "1_1") (pintype "passive"))
    )
    (net (code "40") (name "Net-(U1-XTAL1)") (class "Default")
      (node (ref "C16") (pin "1") (pinfunction "1_1") (pintype "passive"))
      (node (ref "U1") (pin "8") (pinfunction "XTAL1_8") (pintype "bidirectional"))
      (node (ref "Y1") (pin "2") (pinfunction "2_2") (pintype "passive"))
    )
    (net (code "41") (name "Net-(U1-XTAL2)") (class "Default")
      (node (ref "C15") (pin "1") (pinfunction "1_1") (pintype "passive"))
      (node (ref "U1") (pin "7") (pinfunction "XTAL2_7") (pintype "bidirectional"))
      (node (ref "Y1") (pin "1") (pinfunction "1_1") (pintype "passive"))
    )
    (net (code "42") (name "Net-(U3A-A)") (class "Default")
      (node (ref "C7") (pin "1") (pinfunction "1_1") (pintype "passive"))
      (node (ref "MENU") (pin "1") (pinfunction "S_1") (pintype "passive"))
      (node (ref "MENU") (pin "2") (pinfunction "S_2") (pintype "passive"))
      (node (ref "R11") (pin "2") (pinfunction "2_2") (pintype "passive"))
      (node (ref "U3") (pin "1") (pinfunction "A_1") (pintype "tri_state"))
    )
    (net (code "43") (name "Net-(U3B-A)") (class "Default")
      (node (ref "C5") (pin "1") (pinfunction "1_1") (pintype "passive"))
      (node (ref "R10") (pin "2") (pinfunction "2_2") (pintype "passive"))
      (node (ref "RIGHT") (pin "1") (pinfunction "S_1") (pintype "passive"))
      (node (ref "RIGHT") (pin "2") (pinfunction "S_2") (pintype "passive"))
      (node (ref "U3") (pin "4") (pinfunction "A_4") (pintype "tri_state"))
    )
    (net (code "44") (name "Net-(U3C-A)") (class "Default")
      (node (ref "C4") (pin "1") (pinfunction "1_1") (pintype "passive"))
      (node (ref "OK") (pin "1") (pinfunction "S_1") (pintype "passive"))
      (node (ref "OK") (pin "2") (pinfunction "S_2") (pintype "passive"))
      (node (ref "R9") (pin "2") (pinfunction "2_2") (pintype "passive"))
      (node (ref "U3") (pin "8") (pinfunction "A_8") (pintype "tri_state"))
    )
    (net (code "45") (name "Net-(U3D-A)") (class "Default")
      (node (ref "C3") (pin "1") (pinfunction "1_1") (pintype "passive"))
      (node (ref "LEFT") (pin "1") (pinfunction "S_1") (pintype "passive"))
      (node (ref "LEFT") (pin "2") (pinfunction "S_2") (pintype "passive"))
      (node (ref "R8") (pin "2") (pinfunction "2_2") (pintype "passive"))
      (node (ref "U3") (pin "11") (pinfunction "A_11") (pintype "tri_state"))
    )
    (net (code "46") (name "Net-(U8B-VOUT_A)") (class "Default")
      (node (ref "R42") (pin "1") (pinfunction "1_1") (pintype "passive"))
      (node (ref "U8B") (pin "8") (pinfunction "VOUT_A_8") (pintype "output"))
    )
    (net (code "47") (name "Net-(U8B-VOUT_B)") (class "Default")
      (node (ref "R31") (pin "1") (pinfunction "1_1") (pintype "passive"))
      (node (ref "U8B") (pin "5") (pinfunction "VOUT_B_5") (pintype "output"))
    )
    (net (code "48") (name "Net-(U10A-+IN)") (class "Default")
      (node (ref "R31") (pin "2") (pinfunction "2_2") (pintype "passive"))
      (node (ref "R32") (pin "1") (pinfunction "1_1") (pintype "passive"))
      (node (ref "R33") (pin "2") (pinfunction "2_2") (pintype "passive"))
      (node (ref "U10") (pin "3") (pinfunction "+IN_3") (pintype "input"))
    )
    (net (code "49") (name "Net-(U10A--IN)") (class "Default")
      (node (ref "R34") (pin "1") (pinfunction "1_1") (pintype "passive"))
      (node (ref "R35") (pin "2") (pinfunction "2_2") (pintype "passive"))
      (node (ref "R36") (pin "1") (pinfunction "1_1") (pintype "passive"))
      (node (ref "U10") (pin "2") (pinfunction "-IN_2") (pintype "input"))
    )
    (net (code "50") (name "Net-(U10A-OUT)") (class "Default")
      (node (ref "R36") (pin "2") (pinfunction "2_2") (pintype "passive"))
      (node (ref "R39") (pin "1") (pinfunction "1_1") (pintype "passive"))
      (node (ref "U10") (pin "1") (pinfunction "OUT_1") (pintype "output"))
    )
    (net (code "51") (name "Net-(U10B-+IN)") (class "Default")
      (node (ref "R42") (pin "2") (pinfunction "2_2") (pintype "passive"))
      (node (ref "R43") (pin "1") (pinfunction "1_1") (pintype "passive"))
      (node (ref "R44") (pin "2") (pinfunction "2_2") (pintype "passive"))
      (node (ref "U10") (pin "5") (pinfunction "+IN_5") (pintype "input"))
    )
    (net (code "52") (name "Net-(U10B--IN)") (class "Default")
      (node (ref "R45") (pin "1") (pinfunction "1_1") (pintype "passive"))
      (node (ref "R46") (pin "2") (pinfunction "2_2") (pintype "passive"))
      (node (ref "R47") (pin "1") (pinfunction "1_1") (pintype "passive"))
      (node (ref "U10") (pin "6") (pinfunction "-IN_6") (pintype "input"))
    )
    (net (code "53") (name "Net-(U10B-OUT)") (class "Default")
      (node (ref "R47") (pin "2") (pinfunction "2_2") (pintype "passive"))
      (node (ref "R50") (pin "1") (pinfunction "1_1") (pintype "passive"))
      (node (ref "U10") (pin "7") (pinfunction "OUT_7") (pintype "output"))
    )
    (net (code "54") (name "PA0") (class "Default")
      (node (ref "Q1") (pin "3") (pinfunction "S_3") (pintype "passive"))
      (node (ref "Q2") (pin "3") (pinfunction "S_3") (pintype "passive"))
      (node (ref "Q4") (pin "3") (pinfunction "S_3") (pintype "passive"))
      (node (ref "Q5") (pin "3") (pinfunction "S_3") (pintype "passive"))
      (node (ref "R30") (pin "2") (pinfunction "2_2") (pintype "passive"))
      (node (ref "R30_2") (pin "2") (pinfunction "2_2") (pintype "passive"))
      (node (ref "U1") (pin "37") (pinfunction "(ADC0)PA0_37") (pintype "bidirectional"))
    )
    (net (code "55") (name "PA1") (class "Default")
      (node (ref "MULTI") (pin "2") (pinfunction "S_2") (pintype "passive"))
      (node (ref "U1") (pin "36") (pinfunction "(ADC1)PA1_36") (pintype "bidirectional"))
    )
    (net (code "56") (name "PA4") (class "Default")
      (node (ref "LEVEL_A") (pin "2") (pinfunction "S_2") (pintype "passive"))
      (node (ref "U1") (pin "33") (pinfunction "(ADC4)PA4_33") (pintype "bidirectional"))
    )
    (net (code "57") (name "PA5") (class "Default")
      (node (ref "LEVEL_B") (pin "2") (pinfunction "S_2") (pintype "passive"))
      (node (ref "U1") (pin "32") (pinfunction "(ADC5)PA5_32") (pintype "bidirectional"))
    )
    (net (code "58") (name "PB0") (class "Default")
      (node (ref "R48") (pin "2") (pinfunction "2_2") (pintype "passive"))
      (node (ref "R49") (pin "1") (pinfunction "1_1") (pintype "passive"))
      (node (ref "U1") (pin "40") (pinfunction "(T0/XCK)PB0_40") (pintype "bidirectional"))
    )
    (net (code "59") (name "PB1") (class "Default")
      (node (ref "R51") (pin "2") (pinfunction "2_2") (pintype "passive"))
      (node (ref "R52") (pin "1") (pinfunction "1_1") (pintype "passive"))
      (node (ref "U1") (pin "41") (pinfunction "(T1)PB1_41") (pintype "bidirectional"))
    )
    (net (code "60") (name "PB2") (class "Default")
      (node (ref "R37") (pin "2") (pinfunction "2_2") (pintype "passive"))
      (node (ref "R38") (pin "1") (pinfunction "1_1") (pintype "passive"))
      (node (ref "U1") (pin "42") (pinfunction "(AIN0/INT2)PB2_42") (pintype "bidirectional"))
    )
    (net (code "61") (name "PB3") (class "Default")
      (node (ref "R40") (pin "2") (pinfunction "2_2") (pintype "passive"))
      (node (ref "R41") (pin "1") (pinfunction "1_1") (pintype "passive"))
      (node (ref "U1") (pin "43") (pinfunction "(AIN1/OC0)PB3_43") (pintype "bidirectional"))
    )
    (net (code "62") (name "PB5") (class "Default")
      (node (ref "ISP1") (pin "4") (pinfunction "MOSI_4") (pintype "output"))
      (node (ref "U1") (pin "1") (pinfunction "(MOSI)PB5_1") (pintype "bidirectional"))
      (node (ref "U8B") (pin "3") (pinfunction "D_IN_3") (pintype "input"))
    )
    (net (code "63") (name "PB6") (class "Default")
      (node (ref "ISP1") (pin "1") (pinfunction "MISO_1") (pintype "input"))
      (node (ref "U1") (pin "2") (pinfunction "(MISO)PB6_2") (pintype "bidirectional"))
    )
    (net (code "64") (name "PB7") (class "Default")
      (node (ref "ISP1") (pin "3") (pinfunction "SCK_3") (pintype "output"))
      (node (ref "U1") (pin "3") (pinfunction "(SCK)PB7_3") (pintype "bidirectional"))
      (node (ref "U8B") (pin "2") (pinfunction "SCK_2") (pintype "input"))
    )
    (net (code "65") (name "PC0") (class "Default")
      (node (ref "U1") (pin "19") (pinfunction "PC0(SCL)_19") (pintype "bidirectional"))
      (node (ref "U3") (pin "12") (pinfunction "C_12") (pintype "input"))
      (node (ref "U3") (pin "13") (pinfunction "C_13") (pintype "input"))
      (node (ref "U3") (pin "5") (pinfunction "C_5") (pintype "input"))
      (node (ref "U3") (pin "6") (pinfunction "C_6") (pintype "input"))
    )
    (net (code "66") (name "PC1") (class "Default")
      (node (ref "LCD1") (pin "5") (pinfunction "RW_5") (pintype "input"))
      (node (ref "U1") (pin "20") (pinfunction "PC1(SDA)_20") (pintype "bidirectional"))
    )
    (net (code "67") (name "PC2") (class "Default")
      (node (ref "LCD1") (pin "6") (pinfunction "E_6") (pintype "input"))
      (node (ref "U1") (pin "21") (pinfunction "(TCK)PC2_21") (pintype "bidirectional"))
    )
    (net (code "68") (name "PC3") (class "Default")
      (node (ref "LCD1") (pin "4") (pinfunction "RS_4") (pintype "input"))
      (node (ref "U1") (pin "22") (pinfunction "(TMS)PC3_22") (pintype "bidirectional"))
    )
    (net (code "69") (name "PC4") (class "Default")
      (node (ref "LCD1") (pin "11") (pinfunction "DB4_11") (pintype "bidirectional"))
      (node (ref "U1") (pin "23") (pinfunction "(TDO)PC4_23") (pintype "bidirectional"))
      (node (ref "U3") (pin "10") (pinfunction "B_10") (pintype "tri_state"))
    )
    (net (code "70") (name "PC5") (class "Default")
      (node (ref "LCD1") (pin "12") (pinfunction "DB5_12") (pintype "bidirectional"))
      (node (ref "U1") (pin "24") (pinfunction "(TDI)PC5_24") (pintype "bidirectional"))
      (node (ref "U3") (pin "9") (pinfunction "B_9") (pintype "tri_state"))
    )
    (net (code "71") (name "PC6") (class "Default")
      (node (ref "LCD1") (pin "13") (pinfunction "DB6_13") (pintype "bidirectional"))
      (node (ref "U1") (pin "25") (pinfunction "(TOSC1)PC6_25") (pintype "bidirectional"))
      (node (ref "U3") (pin "3") (pinfunction "B_3") (pintype "tri_state"))
    )
    (net (code "72") (name "PC7") (class "Default")
      (node (ref "LCD1") (pin "14") (pinfunction "DB7_14") (pintype "bidirectional"))
      (node (ref "U1") (pin "26") (pinfunction "(TOSC2)PC7_26") (pintype "bidirectional"))
      (node (ref "U3") (pin "2") (pinfunction "B_2") (pintype "tri_state"))
    )
    (net (code "73") (name "PD5") (class "Default")
      (node (ref "LED_CH_B") (pin "K") (pinfunction "C_K") (pintype "passive"))
      (node (ref "U1") (pin "14") (pinfunction "(OC1A)PD5_14") (pintype "bidirectional"))
    )
    (net (code "74") (name "PD6") (class "Default")
      (node (ref "LED_CH_A") (pin "K") (pinfunction "C_K") (pintype "passive"))
      (node (ref "U1") (pin "15") (pinfunction "(ICP)PD6_15") (pintype "bidirectional"))
    )
    (net (code "75") (name "PD7") (class "Default")
      (node (ref "R56") (pin "2") (pinfunction "2_2") (pintype "passive"))
      (node (ref "U1") (pin "16") (pinfunction "(OC2)PD7_16") (pintype "bidirectional"))
    )
    (net (code "76") (name "RESET") (class "Default")
      (node (ref "C8") (pin "1") (pinfunction "1_1") (pintype "passive"))
      (node (ref "ISP1") (pin "5") (pinfunction "RST_5") (pintype "output"))
      (node (ref "R3") (pin "1") (pinfunction "1_1") (pintype "passive"))
      (node (ref "U1") (pin "4") (pinfunction "RESET_4") (pintype "input"))
    )
    (net (code "77") (name "unconnected-(CHAN_A-Pad2)") (class "Default")
      (node (ref "CHAN_A") (pin "2") (pinfunction "2_2") (pintype "bidirectional"))
    )
    (net (code "78") (name "unconnected-(CHAN_B-Pad2)") (class "Default")
      (node (ref "CHAN_B") (pin "2") (pinfunction "2_2") (pintype "bidirectional"))
    )
    (net (code "79") (name "unconnected-(DC_IN-SLEEVE_SHUNT-Pad2)") (class "Default")
      (node (ref "DC_IN") (pin "2") (pinfunction "SLEEVE_SHUNT_2") (pintype "bidirectional"))
    )
    (net (code "80") (name "unconnected-(LCD1-DB0-Pad7)") (class "Default")
      (node (ref "LCD1") (pin "7") (pinfunction "DB0_7") (pintype "bidirectional"))
    )
    (net (code "81") (name "unconnected-(LCD1-DB1-Pad8)") (class "Default")
      (node (ref "LCD1") (pin "8") (pinfunction "DB1_8") (pintype "bidirectional"))
    )
    (net (code "82") (name "unconnected-(LCD1-DB2-Pad9)") (class "Default")
      (node (ref "LCD1") (pin "9") (pinfunction "DB2_9") (pintype "bidirectional"))
    )
    (net (code "83") (name "unconnected-(LCD1-DB3-Pad10)") (class "Default")
      (node (ref "LCD1") (pin "10") (pinfunction "DB3_10") (pintype "bidirectional"))
    )
    (net (code "84") (name "unconnected-(TR1-Pad2)") (class "Default")
      (node (ref "TR1") (pin "2") (pinfunction "2_2") (pintype "passive"))
    )
    (net (code "85") (name "unconnected-(TR2-Pad2)") (class "Default")
      (node (ref "TR2") (pin "2") (pinfunction "2_2") (pintype "passive"))
    )
    (net (code "86") (name "unconnected-(U$1-BOOT-Pad7)") (class "Default")
      (node (ref "U$1") (pin "7") (pinfunction "BOOT_7") (pintype "passive"))
    )
    (net (code "87") (name "unconnected-(U$1-PGOOD-Pad1)") (class "Default")
      (node (ref "U$1") (pin "1") (pinfunction "PGOOD_1") (pintype "open_collector"))
    )
    (net (code "88") (name "unconnected-(U$1-SW-Pad6)") (class "Default")
      (node (ref "U$1") (pin "6") (pinfunction "SW_6") (pintype "passive"))
    )
    (net (code "89") (name "unconnected-(U$1-SW_2-Pad5)") (class "Default")
      (node (ref "U$1") (pin "5") (pinfunction "SW_2_5") (pintype "passive"))
    )
    (net (code "90") (name "unconnected-(U1-(INT0)PD2-Pad11)") (class "Default")
      (node (ref "U1") (pin "11") (pinfunction "(INT0)PD2_11") (pintype "bidirectional"))
    )
    (net (code "91") (name "unconnected-(U1-(INT1)PD3-Pad12)") (class "Default")
      (node (ref "U1") (pin "12") (pinfunction "(INT1)PD3_12") (pintype "bidirectional"))
    )
    (net (code "92") (name "unconnected-(U1-(SS)PB4-Pad44)") (class "Default")
      (node (ref "U1") (pin "44") (pinfunction "(SS)PB4_44") (pintype "bidirectional"))
    )
    (net (code "93") (name "~{CS}") (class "Default")
      (node (ref "U1") (pin "13") (pinfunction "(OC1B)PD4_13") (pintype "bidirectional"))
      (node (ref "U8B") (pin "1") (pinfunction "CS/LD_1") (pintype "input"))
    )
  )
)
